# lt3042_sch.net
KiCad netlist of a schematic drawn in Altium Designer
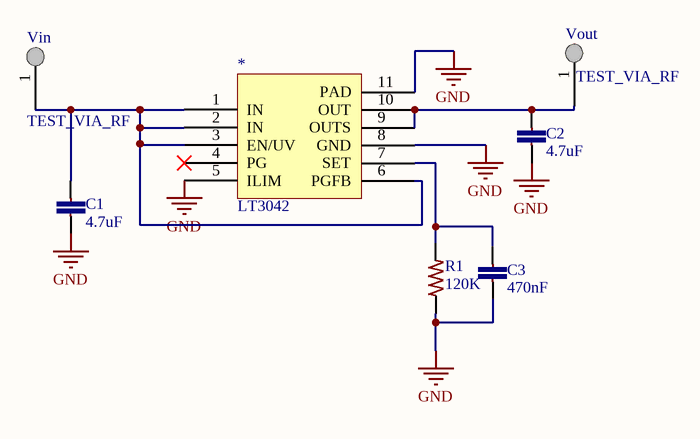
[diagram p0: lt3042_sch.SchDoc]

(export (version "E")
  (design (tool "Eeschema 10.0.6"))
  (components
    (comp (ref "*")
      (value "LT3042")
      (footprint "TSSOP50P490X86-10N")
      (description "IC REG LIN POS ADJ 200MA")
      (libsource (lib "IMBEL") (part "LT3042"))
    )
    (comp (ref "C1")
      (value "4.7uF")
      (footprint "CAPC0603(1608)55_L")
      (description "CAP CER 4.7UF 6.3V 10% X5R 0603")
      (fields (field (name "PART NO") "JMK107BJ475KA-T"))
      (libsource (lib "IMBEL") (part "CAPACITOR"))
    )
    (comp (ref "C2")
      (value "4.7uF")
      (footprint "CAPC0603(1608)55_L")
      (description "CAP CER 4.7UF 6.3V 10% X5R 0603")
      (fields (field (name "PART NO") "JMK107BJ475KA-T"))
      (libsource (lib "IMBEL") (part "CAPACITOR"))
    )
    (comp (ref "C3")
      (value "470nF")
      (footprint "0603-CAP")
      (description "CAP CER 0.47uF 50V 10% X7R 0603")
      (fields (field (name "PART NO") "UMK107B7474KA-TR"))
      (libsource (lib "IMBEL") (part "CAPACITOR"))
    )
    (comp (ref "R1")
      (value "120K")
      (footprint "0603-RES-HD")
      (description "RES SMD 120K OHM 1% 1/10W 0603")
      (fields (field (name "PART NO") "ERJ-3EKF1203V"))
      (libsource (lib "IMBEL") (part "RESISTOR"))
    )
    (comp (ref "Vin")
      (value "TEST_VIA_RF")
      (footprint "New footprint 1")
      (description "Test VIA for RF circuits")
      (libsource (lib "IMBEL") (part "TEST_VIA"))
    )
    (comp (ref "Vout")
      (value "TEST_VIA_RF")
      (footprint "New footprint 1")
      (description "Test VIA for RF circuits")
      (libsource (lib "IMBEL") (part "TEST_VIA"))
    )
  )
  (nets
    (net (code "1") (name "GND") (class "Default")
      (node (ref "*") (pin "11") (pinfunction "PAD_11") (pintype "passive"))
      (node (ref "*") (pin "5") (pinfunction "ILIM_5") (pintype "passive"))
      (node (ref "*") (pin "8") (pinfunction "GND_8") (pintype "passive"))
      (node (ref "C1") (pin "2") (pinfunction "2_2") (pintype "passive"))
      (node (ref "C2") (pin "2") (pinfunction "2_2") (pintype "passive"))
      (node (ref "C3") (pin "2") (pinfunction "2_2") (pintype "passive"))
      (node (ref "R1") (pin "1") (pinfunction "1_1") (pintype "passive"))
    )
    (net (code "2") (name "Net-(*-EN{slash}UV)") (class "Default")
      (node (ref "*") (pin "1") (pinfunction "IN_1") (pintype "passive"))
      (node (ref "*") (pin "2") (pinfunction "IN_2") (pintype "passive"))
      (node (ref "*") (pin "3") (pinfunction "EN/UV_3") (pintype "passive"))
      (node (ref "*") (pin "6") (pinfunction "PGFB_6") (pintype "passive"))
      (node (ref "C1") (pin "1") (pinfunction "1_1") (pintype "passive"))
      (node (ref "Vin") (pin "1") (pinfunction "1_1") (pintype "passive"))
    )
    (net (code "3") (name "Net-(*-OUT)") (class "Default")
      (node (ref "*") (pin "10") (pinfunction "OUT_10") (pintype "passive"))
      (node (ref "*") (pin "9") (pinfunction "OUTS_9") (pintype "passive"))
      (node (ref "C2") (pin "1") (pinfunction "1_1") (pintype "passive"))
      (node (ref "Vout") (pin "1") (pinfunction "1_1") (pintype "passive"))
    )
    (net (code "4") (name "Net-(*-SET)") (class "Default")
      (node (ref "*") (pin "7") (pinfunction "SET_7") (pintype "passive"))
      (node (ref "C3") (pin "1") (pinfunction "1_1") (pintype "passive"))
      (node (ref "R1") (pin "2") (pinfunction "2_2") (pintype "passive"))
    )
    (net (code "5") (name "unconnected-(*-PG-Pad4)") (class "Default")
      (node (ref "*") (pin "4") (pinfunction "PG_4") (pintype "passive+no_connect"))
    )
  )
)
